# PCB-MicroSmartH.net
KiCad netlist of a schematic drawn in EAGLE
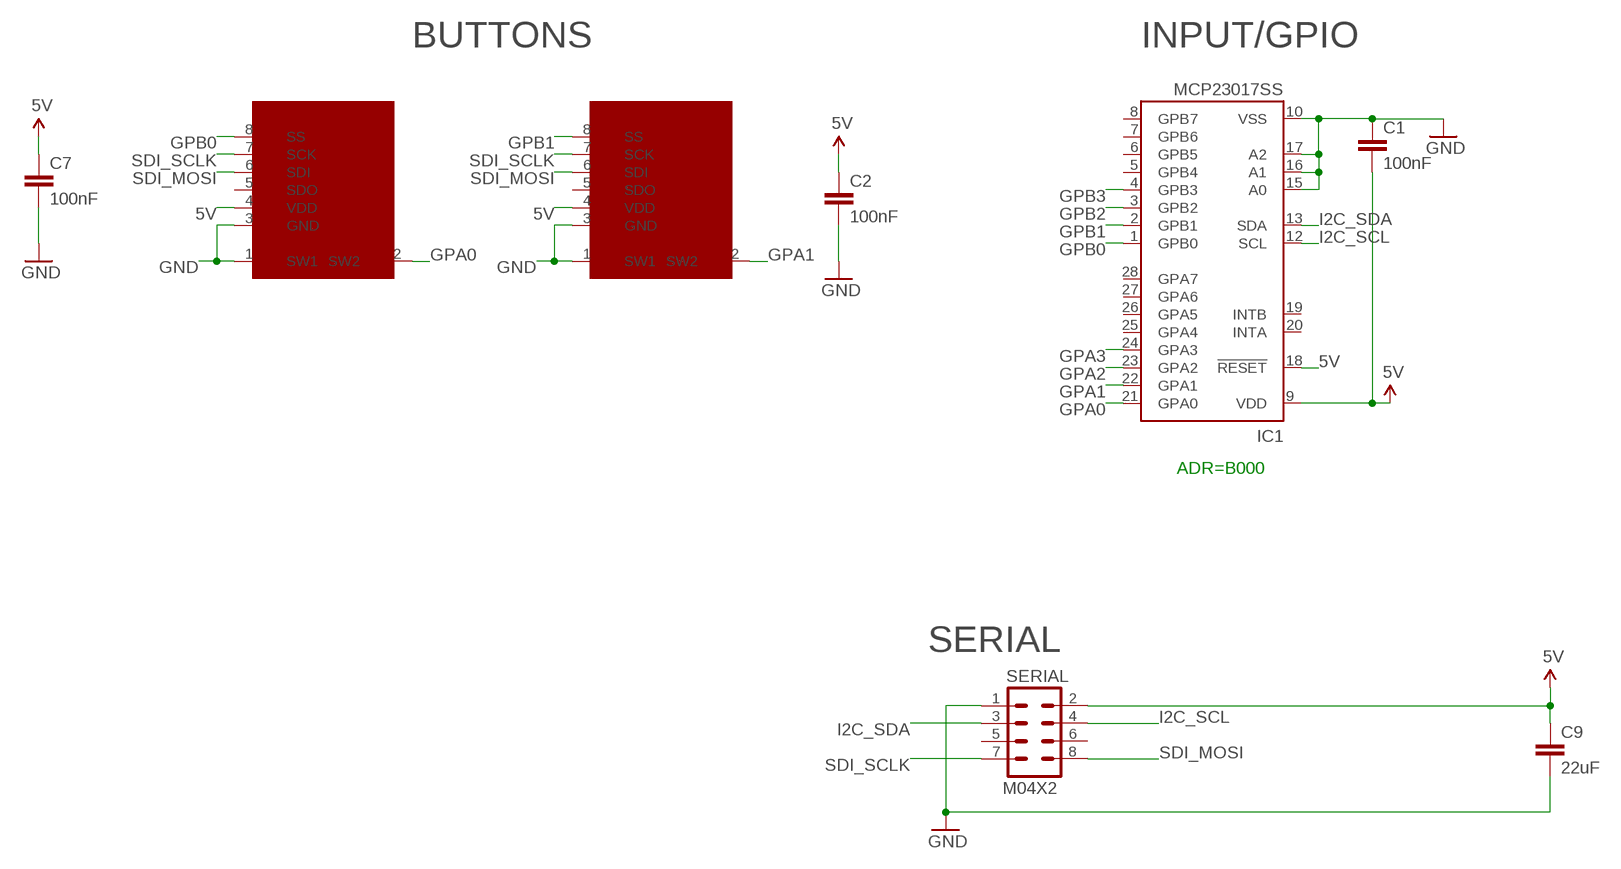
[diagram p0: schematic, sheet 1]

(export (version "E")
  (design (tool "Eeschema 10.0.6"))
  (components
    (comp (ref "C1")
      (value "100nF")
      (footprint "eagle-import:0603-CAP")
      (libsource (lib "eagle-import") (part "CAP0603-CAP"))
    )
    (comp (ref "C2")
      (value "100nF")
      (footprint "eagle-import:0603-CAP")
      (libsource (lib "eagle-import") (part "CAP0603-CAP"))
    )
    (comp (ref "C7")
      (value "100nF")
      (footprint "eagle-import:0603-CAP")
      (libsource (lib "eagle-import") (part "CAP0603-CAP"))
    )
    (comp (ref "C9")
      (value "22uF")
      (footprint "eagle-import:0805")
      (libsource (lib "eagle-import") (part "CAP0805"))
    )
    (comp (ref "IC1")
      (value "MCP23017SS")
      (footprint "eagle-import:SSOP28")
      (fields
        (field (name "MF") "MICROCHIP")
        (field (name "MPN") "MCP23017-E/SS")
        (field (name "MPN_1") "MCP23017-E/SS")
        (field (name "OC_FARNELL") "1467674")
        (field (name "OC_NEWARK") "31K2960")
      )
      (libsource (lib "eagle-import") (part "MCP23017SS"))
    )
    (comp (ref "SERIAL")
      (value "M04X2")
      (footprint "eagle-import:2X4")
      (libsource (lib "eagle-import") (part "M04X2"))
    )
    (comp (ref "SSW1")
      (value "SMART_SWITCHSMART_SWITCH_8PIN")
      (footprint "eagle-import:SMART_SWITCH")
      (libsource (lib "eagle-import") (part "SMART_SWITCHSMART_SWITCH_8PIN"))
    )
    (comp (ref "SSW2")
      (value "SMART_SWITCHSMART_SWITCH_8PIN")
      (footprint "eagle-import:SMART_SWITCH")
      (libsource (lib "eagle-import") (part "SMART_SWITCHSMART_SWITCH_8PIN"))
    )
  )
  (nets
    (net (code "1") (name "/GPA0") (class "Default")
      (node (ref "IC1") (pin "21") (pinfunction "GPA0_21") (pintype "bidirectional"))
      (node (ref "SSW1") (pin "2") (pinfunction "SW2_2") (pintype "bidirectional"))
    )
    (net (code "2") (name "/GPA1") (class "Default")
      (node (ref "IC1") (pin "22") (pinfunction "GPA1_22") (pintype "bidirectional"))
      (node (ref "SSW2") (pin "2") (pinfunction "SW2_2") (pintype "bidirectional"))
    )
    (net (code "3") (name "/GPA2") (class "Default")
      (node (ref "IC1") (pin "23") (pinfunction "GPA2_23") (pintype "bidirectional"))
    )
    (net (code "4") (name "/GPA3") (class "Default")
      (node (ref "IC1") (pin "24") (pinfunction "GPA3_24") (pintype "bidirectional"))
    )
    (net (code "5") (name "/GPB0") (class "Default")
      (node (ref "IC1") (pin "1") (pinfunction "GPB0_1") (pintype "bidirectional"))
      (node (ref "SSW1") (pin "8") (pinfunction "SS_8") (pintype "bidirectional"))
    )
    (net (code "6") (name "/GPB1") (class "Default")
      (node (ref "IC1") (pin "2") (pinfunction "GPB1_2") (pintype "bidirectional"))
      (node (ref "SSW2") (pin "8") (pinfunction "SS_8") (pintype "bidirectional"))
    )
    (net (code "7") (name "/GPB2") (class "Default")
      (node (ref "IC1") (pin "3") (pinfunction "GPB2_3") (pintype "bidirectional"))
    )
    (net (code "8") (name "/GPB3") (class "Default")
      (node (ref "IC1") (pin "4") (pinfunction "GPB3_4") (pintype "bidirectional"))
    )
    (net (code "9") (name "/I2C_SCL") (class "Default")
      (node (ref "IC1") (pin "12") (pinfunction "SCL_12") (pintype "input"))
      (node (ref "SERIAL") (pin "4") (pinfunction "4_4") (pintype "passive"))
    )
    (net (code "10") (name "/I2C_SDA") (class "Default")
      (node (ref "IC1") (pin "13") (pinfunction "SDA_13") (pintype "bidirectional"))
      (node (ref "SERIAL") (pin "3") (pinfunction "3_3") (pintype "passive"))
    )
    (net (code "11") (name "/SDI_MOSI") (class "Default")
      (node (ref "SERIAL") (pin "8") (pinfunction "8_8") (pintype "passive"))
      (node (ref "SSW1") (pin "6") (pinfunction "SDI_6") (pintype "bidirectional"))
      (node (ref "SSW2") (pin "6") (pinfunction "SDI_6") (pintype "bidirectional"))
    )
    (net (code "12") (name "/SDI_SCLK") (class "Default")
      (node (ref "SERIAL") (pin "7") (pinfunction "7_7") (pintype "passive"))
      (node (ref "SSW1") (pin "7") (pinfunction "SCK_7") (pintype "bidirectional"))
      (node (ref "SSW2") (pin "7") (pinfunction "SCK_7") (pintype "bidirectional"))
    )
    (net (code "13") (name "5V") (class "Default")
      (node (ref "C1") (pin "2") (pinfunction "2_2") (pintype "passive"))
      (node (ref "C2") (pin "1") (pinfunction "1_1") (pintype "passive"))
      (node (ref "C7") (pin "1") (pinfunction "1_1") (pintype "passive"))
      (node (ref "C9") (pin "1") (pinfunction "1_1") (pintype "passive"))
      (node (ref "IC1") (pin "18") (pinfunction "~{RESET}_18") (pintype "input"))
      (node (ref "IC1") (pin "9") (pinfunction "VDD_9") (pintype "power_in"))
      (node (ref "SERIAL") (pin "2") (pinfunction "2_2") (pintype "passive"))
      (node (ref "SSW1") (pin "4") (pinfunction "VDD_4") (pintype "bidirectional"))
      (node (ref "SSW2") (pin "4") (pinfunction "VDD_4") (pintype "bidirectional"))
    )
    (net (code "14") (name "GND") (class "Default")
      (node (ref "C1") (pin "1") (pinfunction "1_1") (pintype "passive"))
      (node (ref "C2") (pin "2") (pinfunction "2_2") (pintype "passive"))
      (node (ref "C7") (pin "2") (pinfunction "2_2") (pintype "passive"))
      (node (ref "C9") (pin "2") (pinfunction "2_2") (pintype "passive"))
      (node (ref "IC1") (pin "10") (pinfunction "VSS_10") (pintype "power_in"))
      (node (ref "IC1") (pin "15") (pinfunction "A0_15") (pintype "input"))
      (node (ref "IC1") (pin "16") (pinfunction "A1_16") (pintype "input"))
      (node (ref "IC1") (pin "17") (pinfunction "A2_17") (pintype "input"))
      (node (ref "SERIAL") (pin "1") (pinfunction "1_1") (pintype "passive"))
      (node (ref "SSW1") (pin "1") (pinfunction "SW1_1") (pintype "bidirectional"))
      (node (ref "SSW1") (pin "3") (pinfunction "GND_3") (pintype "bidirectional"))
      (node (ref "SSW2") (pin "1") (pinfunction "SW1_1") (pintype "bidirectional"))
      (node (ref "SSW2") (pin "3") (pinfunction "GND_3") (pintype "bidirectional"))
    )
    (net (code "15") (name "unconnected-(IC1-GPA4-Pad25)") (class "Default")
      (node (ref "IC1") (pin "25") (pinfunction "GPA4_25") (pintype "bidirectional"))
    )
    (net (code "16") (name "unconnected-(IC1-GPA5-Pad26)") (class "Default")
      (node (ref "IC1") (pin "26") (pinfunction "GPA5_26") (pintype "bidirectional"))
    )
    (net (code "17") (name "unconnected-(IC1-GPA6-Pad27)") (class "Default")
      (node (ref "IC1") (pin "27") (pinfunction "GPA6_27") (pintype "bidirectional"))
    )
    (net (code "18") (name "unconnected-(IC1-GPA7-Pad28)") (class "Default")
      (node (ref "IC1") (pin "28") (pinfunction "GPA7_28") (pintype "bidirectional"))
    )
    (net (code "19") (name "unconnected-(IC1-GPB4-Pad5)") (class "Default")
      (node (ref "IC1") (pin "5") (pinfunction "GPB4_5") (pintype "bidirectional"))
    )
    (net (code "20") (name "unconnected-(IC1-GPB5-Pad6)") (class "Default")
      (node (ref "IC1") (pin "6") (pinfunction "GPB5_6") (pintype "bidirectional"))
    )
    (net (code "21") (name "unconnected-(IC1-GPB6-Pad7)") (class "Default")
      (node (ref "IC1") (pin "7") (pinfunction "GPB6_7") (pintype "bidirectional"))
    )
    (net (code "22") (name "unconnected-(IC1-GPB7-Pad8)") (class "Default")
      (node (ref "IC1") (pin "8") (pinfunction "GPB7_8") (pintype "bidirectional"))
    )
    (net (code "23") (name "unconnected-(IC1-INTA-Pad20)") (class "Default")
      (node (ref "IC1") (pin "20") (pinfunction "INTA_20") (pintype "output"))
    )
    (net (code "24") (name "unconnected-(IC1-INTB-Pad19)") (class "Default")
      (node (ref "IC1") (pin "19") (pinfunction "INTB_19") (pintype "output"))
    )
    (net (code "25") (name "unconnected-(SERIAL-Pad5)") (class "Default")
      (node (ref "SERIAL") (pin "5") (pinfunction "5_5") (pintype "passive"))
    )
    (net (code "26") (name "unconnected-(SERIAL-Pad6)") (class "Default")
      (node (ref "SERIAL") (pin "6") (pinfunction "6_6") (pintype "passive"))
    )
    (net (code "27") (name "unconnected-(SSW1-SDO-Pad5)") (class "Default")
      (node (ref "SSW1") (pin "5") (pinfunction "SDO_5") (pintype "bidirectional"))
    )
    (net (code "28") (name "unconnected-(SSW2-SDO-Pad5)") (class "Default")
      (node (ref "SSW2") (pin "5") (pinfunction "SDO_5") (pintype "bidirectional"))
    )
  )
)
